# ZC_det.net
KiCad netlist of a schematic drawn in EAGLE
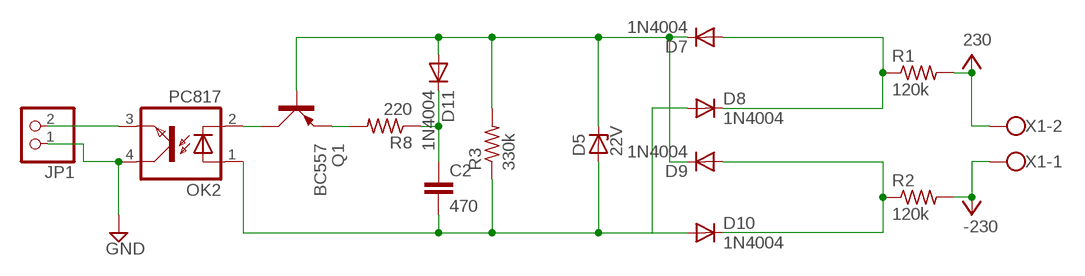
[diagram p0: schematic, sheet 1]

(export (version "E")
  (design (tool "Eeschema 10.0.6"))
  (components
    (comp (ref "C2")
      (value "470")
      (footprint "eagle-import:C025_050-025X075")
      (libsource (lib "eagle-import") (part "C-EU025_050-025X075"))
    )
    (comp (ref "D5")
      (value "22V")
      (footprint "eagle-import:ZDIO-7.5")
      (libsource (lib "eagle-import") (part "ZENER-DIODEZD-7.5"))
    )
    (comp (ref "D7")
      (value "1N4004")
      (footprint "eagle-import:DO41-10")
      (libsource (lib "eagle-import") (part "1N4004"))
    )
    (comp (ref "D8")
      (value "1N4004")
      (footprint "eagle-import:DO41-10")
      (libsource (lib "eagle-import") (part "1N4004"))
    )
    (comp (ref "D9")
      (value "1N4004")
      (footprint "eagle-import:DO41-10")
      (libsource (lib "eagle-import") (part "1N4004"))
    )
    (comp (ref "D10")
      (value "1N4004")
      (footprint "eagle-import:DO41-10")
      (libsource (lib "eagle-import") (part "1N4004"))
    )
    (comp (ref "D11")
      (value "1N4004")
      (footprint "eagle-import:DO41-10")
      (libsource (lib "eagle-import") (part "1N4004"))
    )
    (comp (ref "JP1")
      (value "PINHD-1X2")
      (footprint "eagle-import:1X02")
      (libsource (lib "eagle-import") (part "PINHD-1X2"))
    )
    (comp (ref "OK2")
      (value "PC817")
      (footprint "eagle-import:DIL04")
      (fields (field (name "MPN") "PC817X4J000F"))
      (libsource (lib "eagle-import") (part "PC817"))
    )
    (comp (ref "Q1")
      (value "BC557")
      (footprint "eagle-import:SOT54A")
      (libsource (lib "eagle-import") (part "BC557"))
    )
    (comp (ref "R1")
      (value "120k")
      (footprint "eagle-import:0207_7")
      (libsource (lib "eagle-import") (part "R-US_0207/7"))
    )
    (comp (ref "R2")
      (value "120k")
      (footprint "eagle-import:0207_7")
      (libsource (lib "eagle-import") (part "R-US_0207/7"))
    )
    (comp (ref "R3")
      (value "330k")
      (footprint "eagle-import:0207_7")
      (libsource (lib "eagle-import") (part "R-US_0207/7"))
    )
    (comp (ref "R8")
      (value "220")
      (footprint "eagle-import:0207_7")
      (libsource (lib "eagle-import") (part "R-US_0207/7"))
    )
    (comp (ref "X1")
      (value "W237-102")
      (footprint "eagle-import:W237-102")
      (fields (field (name "MPN") "237-102"))
      (libsource (lib "eagle-import") (part "W237-102"))
    )
  )
  (nets
    (net (code "1") (name "-230") (class "Default")
      (node (ref "R2") (pin "2") (pinfunction "2_2") (pintype "passive"))
      (node (ref "X1") (pin "1") (pinfunction "KL_1") (pintype "passive"))
    )
    (net (code "2") (name "230") (class "Default")
      (node (ref "R1") (pin "2") (pinfunction "2_2") (pintype "passive"))
      (node (ref "X1") (pin "2") (pinfunction "KL_2") (pintype "passive"))
    )
    (net (code "3") (name "GND") (class "Default")
      (node (ref "JP1") (pin "1") (pinfunction "1_1") (pintype "passive"))
      (node (ref "OK2") (pin "4") (pinfunction "COL_4") (pintype "passive"))
    )
    (net (code "4") (name "Net-(C2-Pad1)") (class "Default")
      (node (ref "C2") (pin "1") (pinfunction "1_1") (pintype "passive"))
      (node (ref "D11") (pin "C") (pinfunction "C_C") (pintype "passive"))
      (node (ref "R8") (pin "1") (pinfunction "1_1") (pintype "passive"))
    )
    (net (code "5") (name "Net-(D7-PadA)") (class "Default")
      (node (ref "D7") (pin "A") (pinfunction "A_A") (pintype "passive"))
      (node (ref "D8") (pin "C") (pinfunction "C_C") (pintype "passive"))
      (node (ref "R1") (pin "1") (pinfunction "1_1") (pintype "passive"))
    )
    (net (code "6") (name "Net-(D10-PadC)") (class "Default")
      (node (ref "D10") (pin "C") (pinfunction "C_C") (pintype "passive"))
      (node (ref "D9") (pin "A") (pinfunction "A_A") (pintype "passive"))
      (node (ref "R2") (pin "1") (pinfunction "1_1") (pintype "passive"))
    )
    (net (code "7") (name "Net-(D11-PadA)") (class "Default")
      (node (ref "D11") (pin "A") (pinfunction "A_A") (pintype "passive"))
      (node (ref "D5") (pin "C") (pinfunction "C_C") (pintype "passive"))
      (node (ref "D7") (pin "C") (pinfunction "C_C") (pintype "passive"))
      (node (ref "D9") (pin "C") (pinfunction "C_C") (pintype "passive"))
      (node (ref "Q1") (pin "B") (pinfunction "B_B") (pintype "passive"))
      (node (ref "R3") (pin "2") (pinfunction "2_2") (pintype "passive"))
    )
    (net (code "8") (name "Net-(OK2-A)") (class "Default")
      (node (ref "C2") (pin "2") (pinfunction "2_2") (pintype "passive"))
      (node (ref "D10") (pin "A") (pinfunction "A_A") (pintype "passive"))
      (node (ref "D5") (pin "A") (pinfunction "A_A") (pintype "passive"))
      (node (ref "D8") (pin "A") (pinfunction "A_A") (pintype "passive"))
      (node (ref "OK2") (pin "1") (pinfunction "A_1") (pintype "passive"))
      (node (ref "R3") (pin "1") (pinfunction "1_1") (pintype "passive"))
    )
    (net (code "9") (name "Net-(OK2-C)") (class "Default")
      (node (ref "OK2") (pin "2") (pinfunction "C_2") (pintype "passive"))
      (node (ref "Q1") (pin "C") (pinfunction "C_C") (pintype "passive"))
    )
    (net (code "10") (name "Net-(OK2-EMIT)") (class "Default")
      (node (ref "JP1") (pin "2") (pinfunction "2_2") (pintype "passive"))
      (node (ref "OK2") (pin "3") (pinfunction "EMIT_3") (pintype "passive"))
    )
    (net (code "11") (name "Net-(Q1-PadE)") (class "Default")
      (node (ref "Q1") (pin "E") (pinfunction "E_E") (pintype "passive"))
      (node (ref "R8") (pin "2") (pinfunction "2_2") (pintype "passive"))
    )
  )
)
